# FMC_Delay_1ns_4Cha.net
KiCad netlist of a schematic drawn in Altium Designer
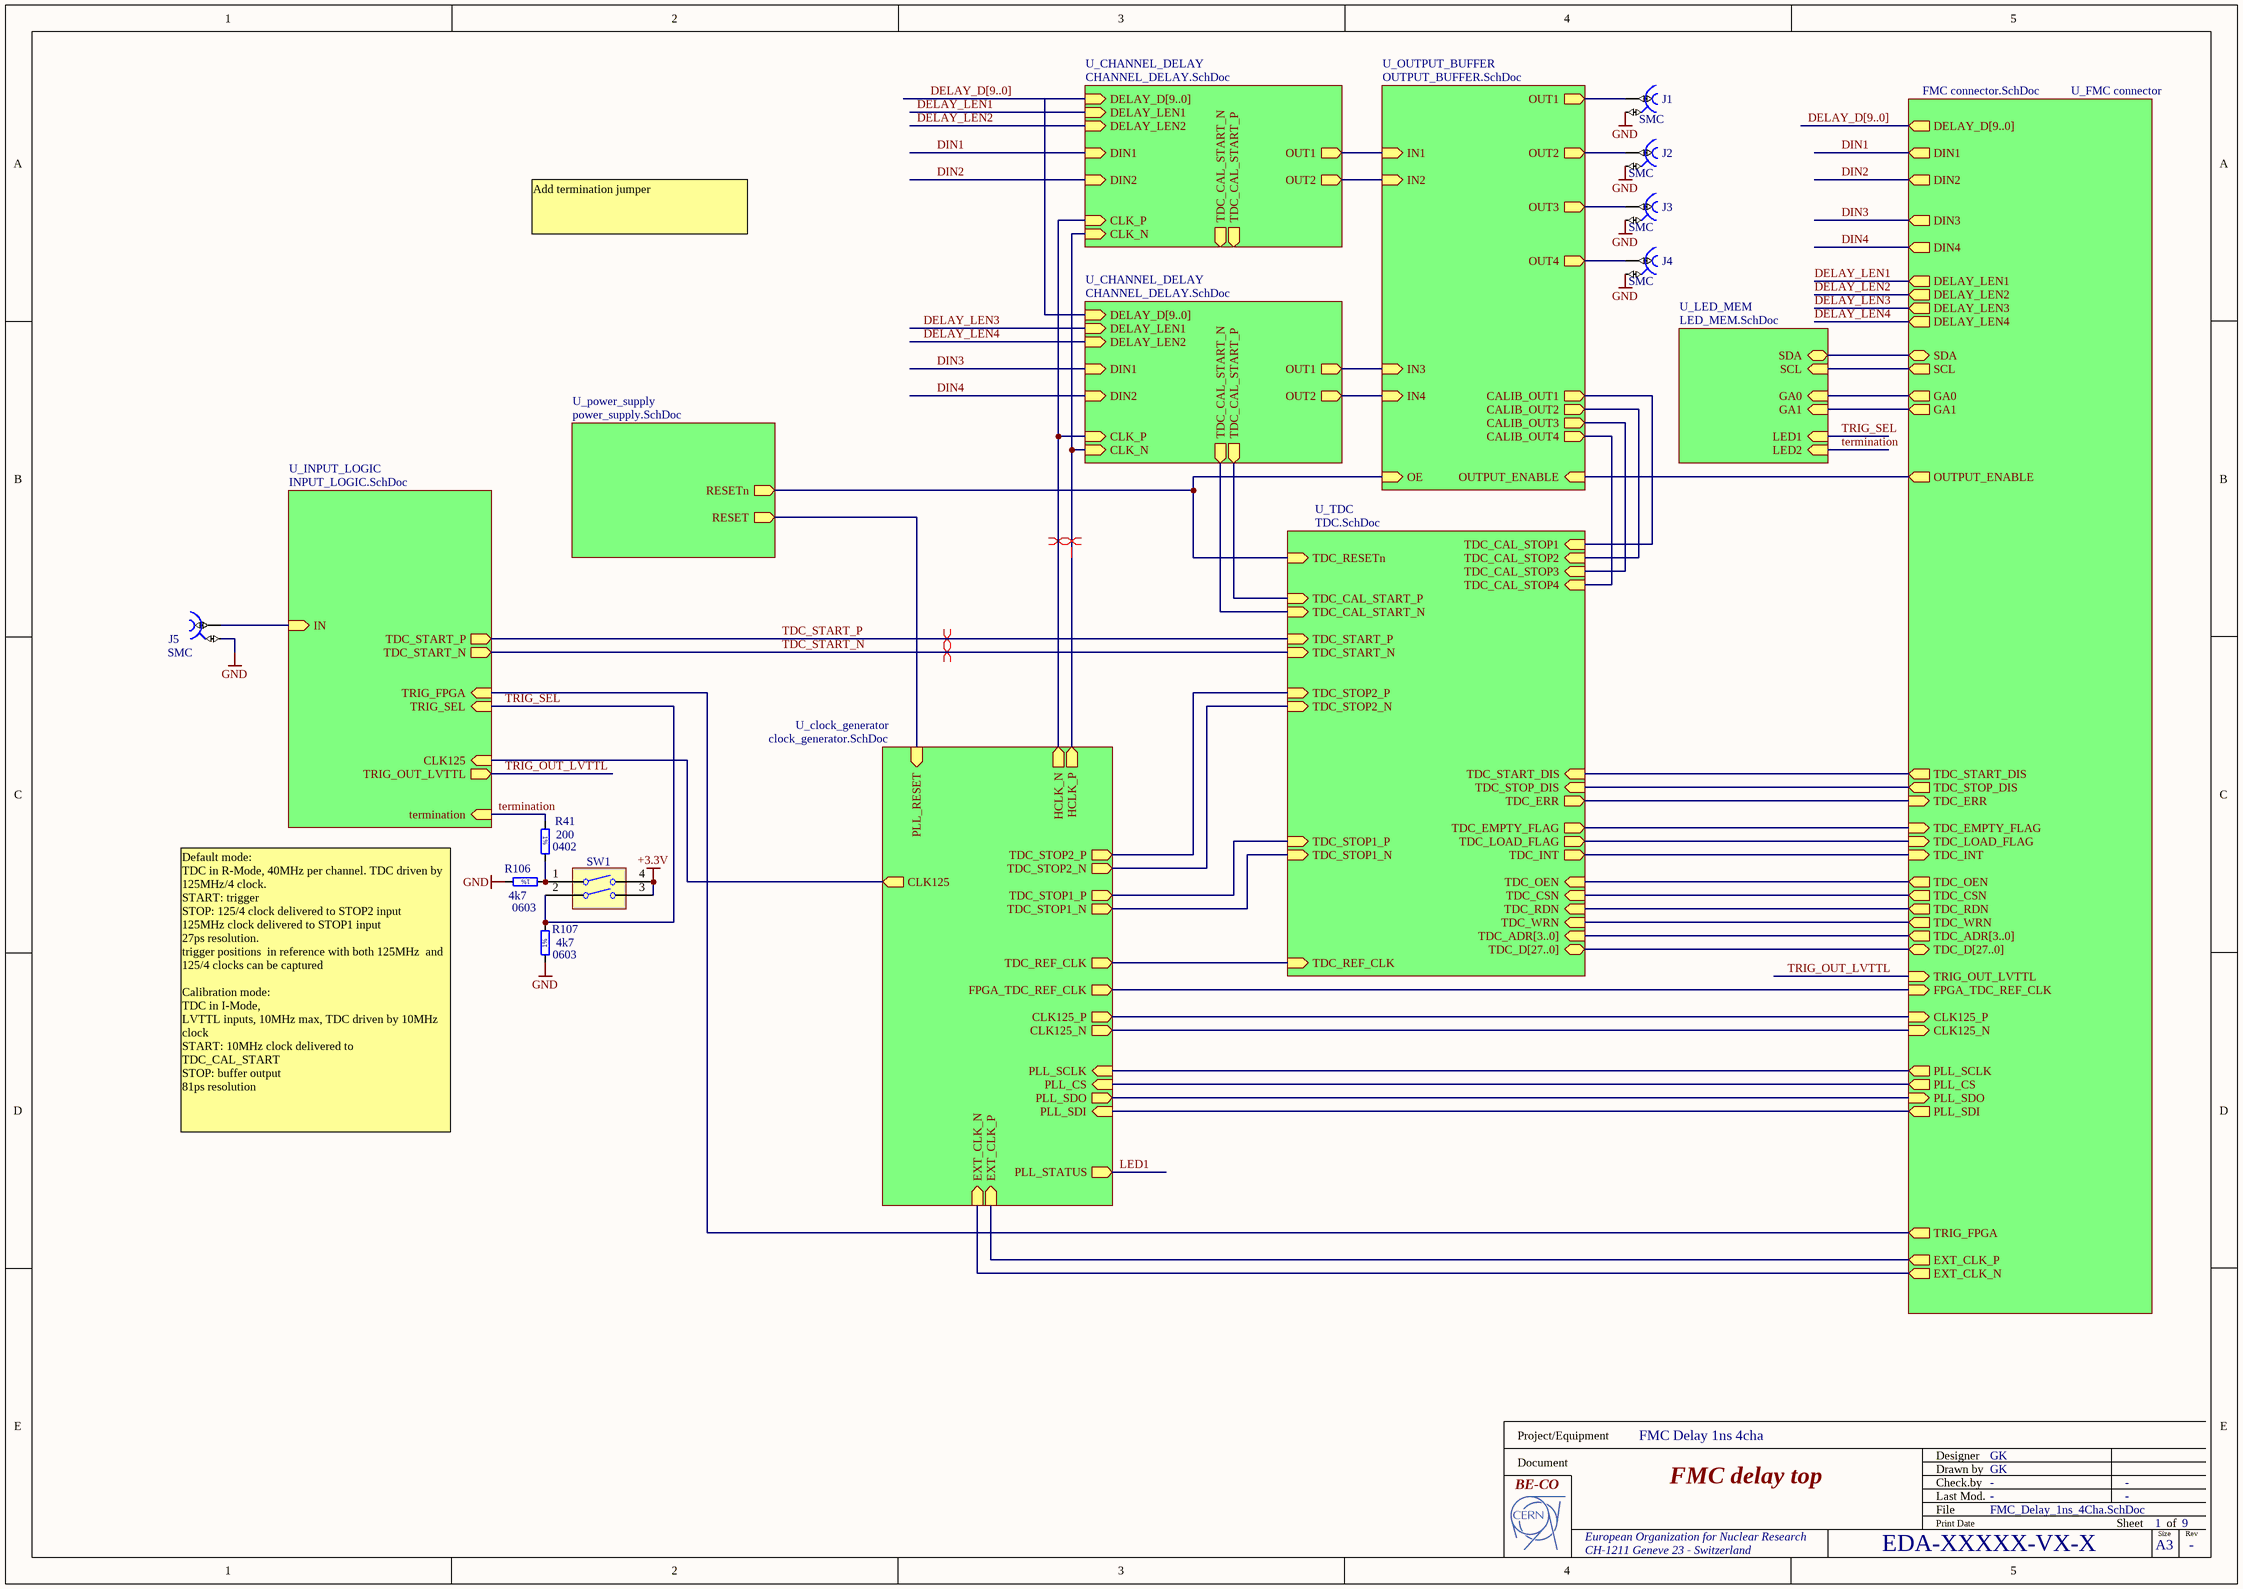
[diagram p0: FMC_Delay_1ns_4Cha.SchDoc]

(export (version "E")
  (design (tool "Eeschema 10.0.6"))
  (components
    (comp (ref "J1")
      (value "SMC")
      (footprint "JOHNSON_131-6701-341")
      (fields
        (field (name "PART NUMBER") "JOHNSON_131-6701-341")
        (field (name "MANUFACTURER") "JOHNSON")
        (field (name "MANUFACTURER PART NUMBER") "142-0701-873")
        (field (name "AUTHOR") "CERN DEM JLC")
      )
      (libsource (lib "Connectors") (part "Coax_1Female_1Shield"))
    )
    (comp (ref "J2")
      (value "SMC")
      (footprint "JOHNSON_131-6701-341")
      (fields
        (field (name "PART NUMBER") "JOHNSON_131-6701-341")
        (field (name "MANUFACTURER") "JOHNSON")
        (field (name "MANUFACTURER PART NUMBER") "142-0701-873")
        (field (name "AUTHOR") "CERN DEM JLC")
      )
      (libsource (lib "Connectors") (part "Coax_1Female_1Shield"))
    )
    (comp (ref "J3")
      (value "SMC")
      (footprint "JOHNSON_131-6701-341")
      (fields
        (field (name "PART NUMBER") "JOHNSON_131-6701-341")
        (field (name "MANUFACTURER") "JOHNSON")
        (field (name "MANUFACTURER PART NUMBER") "142-0701-873")
        (field (name "AUTHOR") "CERN DEM JLC")
      )
      (libsource (lib "Connectors") (part "Coax_1Female_1Shield"))
    )
    (comp (ref "J4")
      (value "SMC")
      (footprint "JOHNSON_131-6701-341")
      (fields
        (field (name "PART NUMBER") "JOHNSON_131-6701-341")
        (field (name "MANUFACTURER") "JOHNSON")
        (field (name "MANUFACTURER PART NUMBER") "142-0701-873")
        (field (name "AUTHOR") "CERN DEM JLC")
      )
      (libsource (lib "Connectors") (part "Coax_1Female_1Shield"))
    )
    (comp (ref "J5")
      (value "SMC")
      (footprint "JOHNSON_131-6701-341")
      (fields
        (field (name "PART NUMBER") "JOHNSON_131-6701-341")
        (field (name "MANUFACTURER") "JOHNSON")
        (field (name "MANUFACTURER PART NUMBER") "142-0701-873")
        (field (name "AUTHOR") "CERN DEM JLC")
      )
      (libsource (lib "") (part "Coax_1Female_1Shield_1"))
    )
    (comp (ref "R41")
      (value "200")
      (footprint "RESC1005X40N")
      (description "Resistor - 1%")
      (fields
        (field (name "PART NUMBER") "R0402_200R_1%_0.0625W_100PPM")
        (field (name "POWER") "0.0625W")
        (field (name "CASE") "0402")
        (field (name "AUTHOR") "CERN DEM JLC")
      )
      (libsource (lib "Resistors") (part "Resistor - 1%"))
    )
    (comp (ref "R106")
      (value "4k7")
      (footprint "RESC1608X55N")
      (description "Resistor - 1%")
      (fields
        (field (name "PART NUMBER") "R0603_4K7_1%_0.1W_100PPM")
        (field (name "POWER") "0.1W")
        (field (name "CASE") "0603")
        (field (name "AUTHOR") "CERN DEM JLC")
      )
      (libsource (lib "Resistors") (part "Resistor - 1%"))
    )
    (comp (ref "R107")
      (value "4k7")
      (footprint "RESC1608X55N")
      (description "Resistor - 1%")
      (fields
        (field (name "PART NUMBER") "R0603_4K7_1%_0.1W_100PPM")
        (field (name "POWER") "0.1W")
        (field (name "CASE") "0603")
        (field (name "AUTHOR") "CERN DEM JLC")
      )
      (libsource (lib "Resistors") (part "Resistor - 1%"))
    )
    (comp (ref "SW1")
      (value "Switch")
      (footprint "SW_TYCO_1571983-1")
      (description "2 Ways SPST DIP Switch")
      (fields
        (field (name "PART NUMBER") "SW_TYCO_1571983-1")
        (field (name "MANUFACTURER") "TYCO")
        (field (name "AUTHOR") "CERN DEM JLC")
      )
      (libsource (lib "Eletro-mechanical") (part "SW 2x SPST DIP Switch"))
    )
  )
  (nets
    (net (code "11") (name "+3.3V") (class "Default")
      (node (ref "SW1") (pin "3") (pinfunction "3_3") (pintype "passive"))
      (node (ref "SW1") (pin "4") (pinfunction "4_4") (pintype "passive"))
    )
    (net (code "35") (name "/IN") (class "Default")
      (node (ref "J5") (pin "1") (pinfunction "1_1") (pintype "bidirectional"))
    )
    (net (code "37") (name "/OUT1") (class "Default")
      (node (ref "J1") (pin "1") (pinfunction "1_1") (pintype "bidirectional"))
    )
    (net (code "40") (name "/OUT2") (class "Default")
      (node (ref "J2") (pin "1") (pinfunction "1_1") (pintype "bidirectional"))
    )
    (net (code "43") (name "/OUT3") (class "Default")
      (node (ref "J3") (pin "1") (pinfunction "1_1") (pintype "bidirectional"))
    )
    (net (code "44") (name "/OUT4") (class "Default")
      (node (ref "J4") (pin "1") (pinfunction "1_1") (pintype "bidirectional"))
    )
    (net (code "79") (name "/TRIG_SEL") (class "Default")
      (node (ref "R107") (pin "2") (pinfunction "2_2") (pintype "passive"))
      (node (ref "SW1") (pin "2") (pinfunction "2_2") (pintype "passive"))
    )
    (net (code "80") (name "/termination") (class "Default")
      (node (ref "R41") (pin "1") (pinfunction "1_1") (pintype "passive"))
    )
    (net (code "81") (name "GND") (class "Default")
      (node (ref "J1") (pin "2") (pinfunction "2_2") (pintype "bidirectional"))
      (node (ref "J2") (pin "2") (pinfunction "2_2") (pintype "bidirectional"))
      (node (ref "J3") (pin "2") (pinfunction "2_2") (pintype "bidirectional"))
      (node (ref "J4") (pin "2") (pinfunction "2_2") (pintype "bidirectional"))
      (node (ref "J5") (pin "2") (pinfunction "2_2") (pintype "bidirectional"))
      (node (ref "R106") (pin "2") (pinfunction "2_2") (pintype "passive"))
      (node (ref "R107") (pin "1") (pinfunction "1_1") (pintype "passive"))
    )
    (net (code "82") (name "Net-(R106-Pad1)") (class "Default")
      (node (ref "R106") (pin "1") (pinfunction "1_1") (pintype "passive"))
      (node (ref "R41") (pin "2") (pinfunction "2_2") (pintype "passive"))
      (node (ref "SW1") (pin "1") (pinfunction "1_1") (pintype "passive"))
    )
  )
)
